# gems-0-01.net
KiCad netlist of a schematic drawn in EAGLE
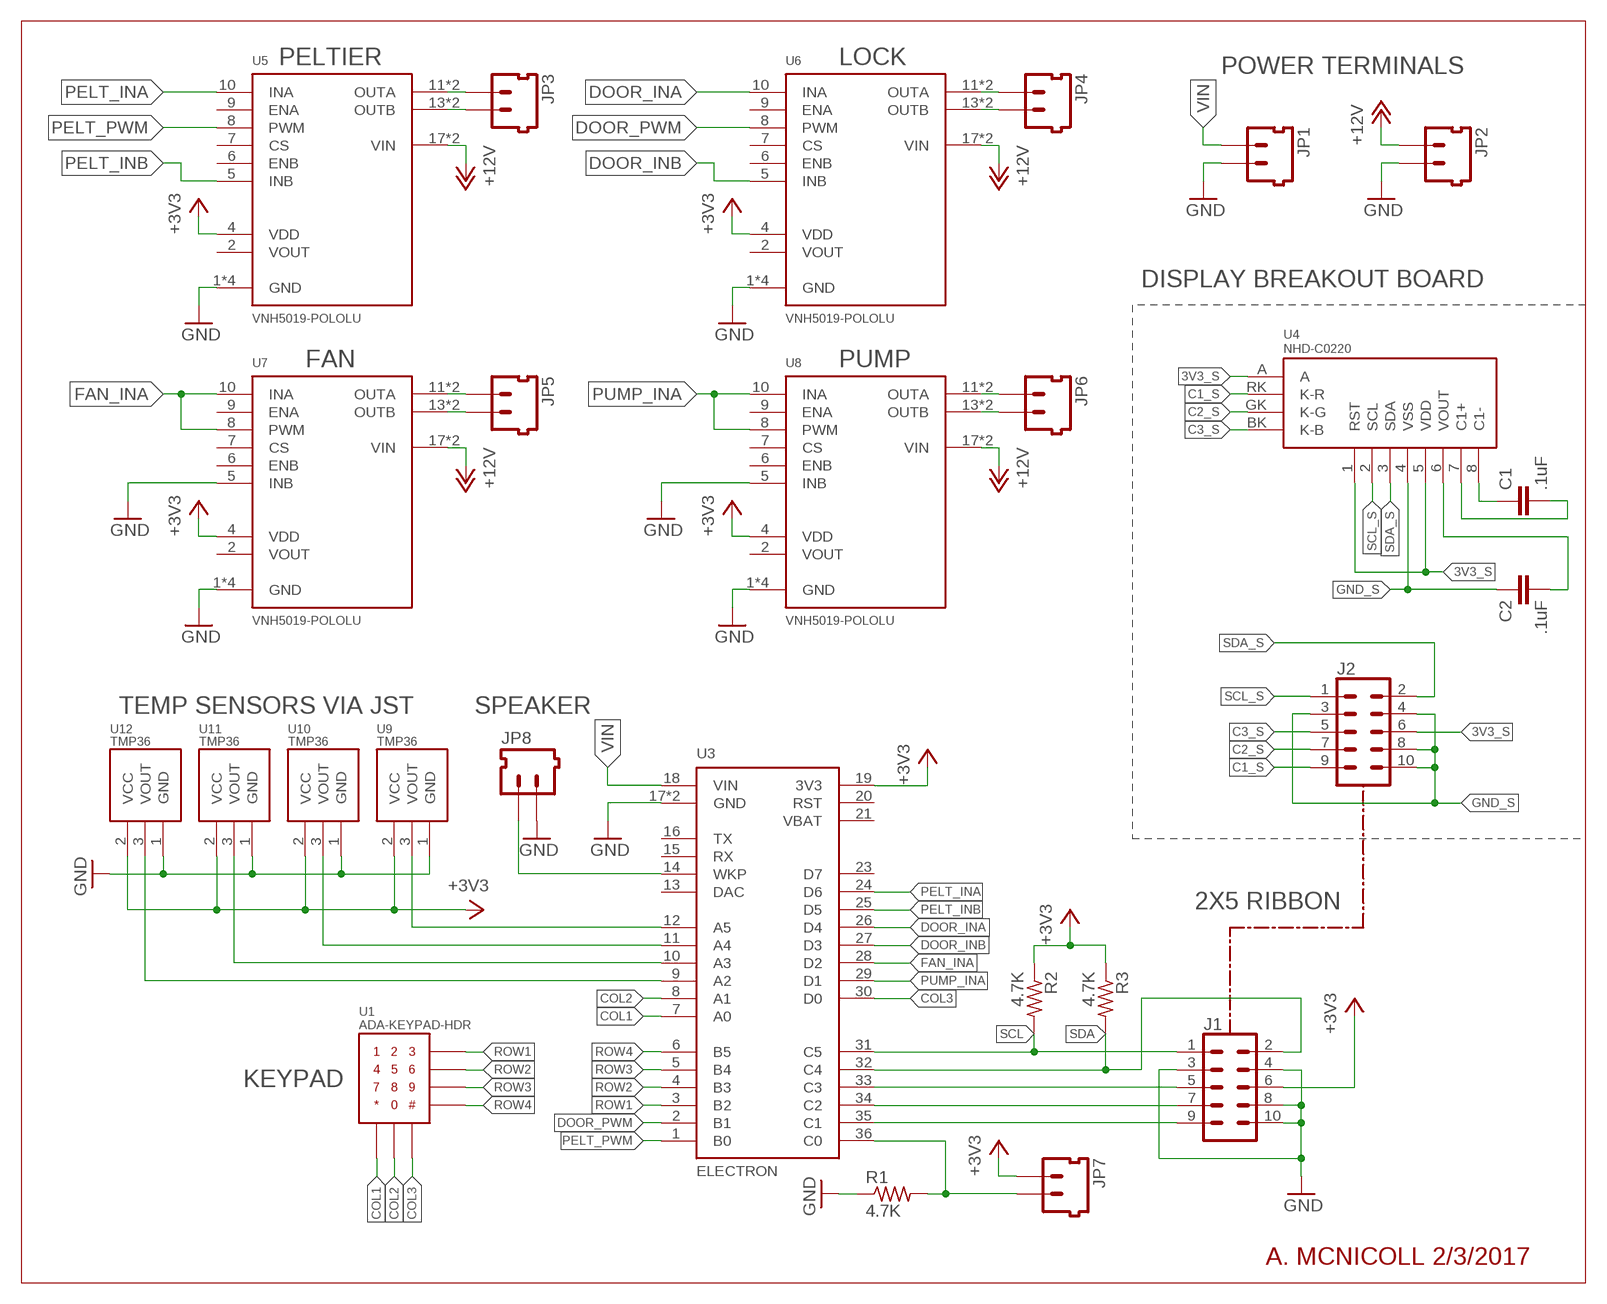
[diagram p0: schematic, sheet 1]

(export (version "E")
  (design (tool "Eeschema 10.0.6"))
  (components
    (comp (ref "C1")
      (value ".1uF")
      (footprint "eagle-import:C025-025X050")
      (libsource (lib "eagle-import") (part "C-EU025-025X050"))
    )
    (comp (ref "C2")
      (value ".1uF")
      (footprint "eagle-import:C025-025X050")
      (libsource (lib "eagle-import") (part "C-EU025-025X050"))
    )
    (comp (ref "J1")
      (value "CONN_05X2SHD-NS")
      (footprint "eagle-import:2X5-SHROUDED-NS")
      (libsource (lib "eagle-import") (part "CONN_05X2SHD-NS"))
    )
    (comp (ref "J2")
      (value "CONN_05X2SHD-NS")
      (footprint "eagle-import:2X5-SHROUDED-NS")
      (libsource (lib "eagle-import") (part "CONN_05X2SHD-NS"))
    )
    (comp (ref "JP1")
      (value "SCREW-TERMINAL-2PIN-5MM-KEYED")
      (footprint "eagle-import:SCREWTERMINAL-5MM-2-DIAG")
      (libsource (lib "eagle-import") (part "SCREW-TERMINAL-2PIN-5MM-KEYED"))
    )
    (comp (ref "JP2")
      (value "SCREW-TERMINAL-2PIN-5MM-KEYED")
      (footprint "eagle-import:SCREWTERMINAL-5MM-2-DIAG")
      (libsource (lib "eagle-import") (part "SCREW-TERMINAL-2PIN-5MM-KEYED"))
    )
    (comp (ref "JP3")
      (value "SCREW-TERMINAL-2PIN-5MM-KEYED")
      (footprint "eagle-import:SCREWTERMINAL-5MM-2-DIAG")
      (libsource (lib "eagle-import") (part "SCREW-TERMINAL-2PIN-5MM-KEYED"))
    )
    (comp (ref "JP4")
      (value "SCREW-TERMINAL-2PIN-5MM-KEYED")
      (footprint "eagle-import:SCREWTERMINAL-5MM-2-DIAG")
      (libsource (lib "eagle-import") (part "SCREW-TERMINAL-2PIN-5MM-KEYED"))
    )
    (comp (ref "JP5")
      (value "SCREW-TERMINAL-2PIN-5MM-KEYED")
      (footprint "eagle-import:SCREWTERMINAL-5MM-2-DIAG")
      (libsource (lib "eagle-import") (part "SCREW-TERMINAL-2PIN-5MM-KEYED"))
    )
    (comp (ref "JP6")
      (value "SCREW-TERMINAL-2PIN-5MM-KEYED")
      (footprint "eagle-import:SCREWTERMINAL-5MM-2-DIAG")
      (libsource (lib "eagle-import") (part "SCREW-TERMINAL-2PIN-5MM-KEYED"))
    )
    (comp (ref "JP7")
      (value "SCREW-TERMINAL-2PIN-5MM-KEYED")
      (footprint "eagle-import:SCREWTERMINAL-5MM-2-DIAG")
      (libsource (lib "eagle-import") (part "SCREW-TERMINAL-2PIN-5MM-KEYED"))
    )
    (comp (ref "JP8")
      (value "SCREW-TERMINAL-2PIN-5MM-KEYED")
      (footprint "eagle-import:SCREWTERMINAL-5MM-2-DIAG")
      (libsource (lib "eagle-import") (part "SCREW-TERMINAL-2PIN-5MM-KEYED"))
    )
    (comp (ref "R1")
      (value "4.7K")
      (footprint "eagle-import:0204_5")
      (libsource (lib "eagle-import") (part "R-US_0204/5"))
    )
    (comp (ref "R2")
      (value "4.7K")
      (footprint "eagle-import:0204_5")
      (libsource (lib "eagle-import") (part "R-US_0204/5"))
    )
    (comp (ref "R3")
      (value "4.7K")
      (footprint "eagle-import:0204_5")
      (libsource (lib "eagle-import") (part "R-US_0204/5"))
    )
    (comp (ref "U1")
      (value "ADA-KEYPAD-HDR")
      (footprint "eagle-import:HDR-7-STAGGERED")
      (libsource (lib "eagle-import") (part "ADA-KEYPAD-HDR"))
    )
    (comp (ref "U3")
      (value "ELECTRON")
      (footprint "eagle-import:ELECTRON")
      (libsource (lib "eagle-import") (part "ELECTRON"))
    )
    (comp (ref "U4")
      (value "NHD‐C0220")
      (footprint "eagle-import:NHD-C0220")
      (libsource (lib "eagle-import") (part "NHD‐C0220"))
    )
    (comp (ref "U5")
      (value "VNH5019-POLOLU")
      (footprint "eagle-import:VNH1519-CARRIER")
      (libsource (lib "eagle-import") (part "VNH5019-POLOLU"))
    )
    (comp (ref "U6")
      (value "VNH5019-POLOLU")
      (footprint "eagle-import:VNH1519-CARRIER")
      (libsource (lib "eagle-import") (part "VNH5019-POLOLU"))
    )
    (comp (ref "U7")
      (value "VNH5019-POLOLU")
      (footprint "eagle-import:VNH1519-CARRIER")
      (libsource (lib "eagle-import") (part "VNH5019-POLOLU"))
    )
    (comp (ref "U8")
      (value "VNH5019-POLOLU")
      (footprint "eagle-import:VNH1519-CARRIER")
      (libsource (lib "eagle-import") (part "VNH5019-POLOLU"))
    )
    (comp (ref "U9")
      (value "TMP36")
      (footprint "eagle-import:JST-3-PTH")
      (libsource (lib "eagle-import") (part "TMP36"))
    )
    (comp (ref "U10")
      (value "TMP36")
      (footprint "eagle-import:JST-3-PTH")
      (libsource (lib "eagle-import") (part "TMP36"))
    )
    (comp (ref "U11")
      (value "TMP36")
      (footprint "eagle-import:JST-3-PTH")
      (libsource (lib "eagle-import") (part "TMP36"))
    )
    (comp (ref "U12")
      (value "TMP36")
      (footprint "eagle-import:JST-3-PTH")
      (libsource (lib "eagle-import") (part "TMP36"))
    )
  )
  (nets
    (net (code "1") (name "+3V3") (class "Default")
      (node (ref "J1") (pin "6") (pinfunction "6_6") (pintype "passive"))
      (node (ref "JP7") (pin "F") (pinfunction "F_F") (pintype "passive"))
      (node (ref "R2") (pin "1") (pinfunction "1_1") (pintype "passive"))
      (node (ref "R3") (pin "1") (pinfunction "1_1") (pintype "passive"))
      (node (ref "U10") (pin "2") (pinfunction "VCC_2") (pintype "bidirectional"))
      (node (ref "U11") (pin "2") (pinfunction "VCC_2") (pintype "bidirectional"))
      (node (ref "U12") (pin "2") (pinfunction "VCC_2") (pintype "bidirectional"))
      (node (ref "U3") (pin "19") (pinfunction "3V3_19") (pintype "bidirectional"))
      (node (ref "U5") (pin "4") (pinfunction "VDD_4") (pintype "bidirectional"))
      (node (ref "U6") (pin "4") (pinfunction "VDD_4") (pintype "bidirectional"))
      (node (ref "U7") (pin "4") (pinfunction "VDD_4") (pintype "bidirectional"))
      (node (ref "U8") (pin "4") (pinfunction "VDD_4") (pintype "bidirectional"))
      (node (ref "U9") (pin "2") (pinfunction "VCC_2") (pintype "bidirectional"))
    )
    (net (code "2") (name "+12V") (class "Default")
      (node (ref "JP2") (pin "F") (pinfunction "F_F") (pintype "passive"))
      (node (ref "U5") (pin "17") (pinfunction "VIN_17") (pintype "bidirectional"))
      (node (ref "U5") (pin "18") (pinfunction "VIN_18") (pintype "bidirectional"))
      (node (ref "U6") (pin "17") (pinfunction "VIN_17") (pintype "bidirectional"))
      (node (ref "U6") (pin "18") (pinfunction "VIN_18") (pintype "bidirectional"))
      (node (ref "U7") (pin "17") (pinfunction "VIN_17") (pintype "bidirectional"))
      (node (ref "U7") (pin "18") (pinfunction "VIN_18") (pintype "bidirectional"))
      (node (ref "U8") (pin "17") (pinfunction "VIN_17") (pintype "bidirectional"))
      (node (ref "U8") (pin "18") (pinfunction "VIN_18") (pintype "bidirectional"))
    )
    (net (code "3") (name "3V3_S") (class "Default")
      (node (ref "J2") (pin "6") (pinfunction "6_6") (pintype "passive"))
      (node (ref "U4") (pin "1") (pinfunction "RST_1") (pintype "bidirectional"))
      (node (ref "U4") (pin "5") (pinfunction "VDD_5") (pintype "bidirectional"))
      (node (ref "U4") (pin "A") (pinfunction "A_A") (pintype "bidirectional"))
    )
    (net (code "4") (name "C1_S") (class "Default")
      (node (ref "J2") (pin "9") (pinfunction "9_9") (pintype "passive"))
      (node (ref "U4") (pin "RK") (pinfunction "K-R_RK") (pintype "bidirectional"))
    )
    (net (code "5") (name "C2_S") (class "Default")
      (node (ref "J2") (pin "7") (pinfunction "7_7") (pintype "passive"))
      (node (ref "U4") (pin "GK") (pinfunction "K-G_GK") (pintype "bidirectional"))
    )
    (net (code "6") (name "C3_S") (class "Default")
      (node (ref "J2") (pin "5") (pinfunction "5_5") (pintype "passive"))
      (node (ref "U4") (pin "BK") (pinfunction "K-B_BK") (pintype "bidirectional"))
    )
    (net (code "7") (name "COL1") (class "Default")
      (node (ref "U1") (pin "5") (pinfunction "C1_5") (pintype "bidirectional"))
      (node (ref "U3") (pin "7") (pinfunction "A0_7") (pintype "bidirectional"))
    )
    (net (code "8") (name "COL2") (class "Default")
      (node (ref "U1") (pin "6") (pinfunction "C2_6") (pintype "bidirectional"))
      (node (ref "U3") (pin "8") (pinfunction "A1_8") (pintype "bidirectional"))
    )
    (net (code "9") (name "COL3") (class "Default")
      (node (ref "U1") (pin "7") (pinfunction "C3_7") (pintype "bidirectional"))
      (node (ref "U3") (pin "30") (pinfunction "D0_30") (pintype "bidirectional"))
    )
    (net (code "10") (name "DOOR_INA") (class "Default")
      (node (ref "U3") (pin "26") (pinfunction "D4_26") (pintype "bidirectional"))
      (node (ref "U6") (pin "10") (pinfunction "INA_10") (pintype "bidirectional"))
    )
    (net (code "11") (name "DOOR_INB") (class "Default")
      (node (ref "U3") (pin "27") (pinfunction "D3_27") (pintype "bidirectional"))
      (node (ref "U6") (pin "5") (pinfunction "INB_5") (pintype "bidirectional"))
    )
    (net (code "12") (name "DOOR_PWM") (class "Default")
      (node (ref "U3") (pin "2") (pinfunction "B1_2") (pintype "bidirectional"))
      (node (ref "U6") (pin "8") (pinfunction "PWM_8") (pintype "bidirectional"))
    )
    (net (code "13") (name "FAN_INA") (class "Default")
      (node (ref "U3") (pin "28") (pinfunction "D2_28") (pintype "bidirectional"))
      (node (ref "U7") (pin "10") (pinfunction "INA_10") (pintype "bidirectional"))
      (node (ref "U7") (pin "8") (pinfunction "PWM_8") (pintype "bidirectional"))
    )
    (net (code "14") (name "GND") (class "Default")
      (node (ref "J1") (pin "10") (pinfunction "10_10") (pintype "passive"))
      (node (ref "J1") (pin "3") (pinfunction "3_3") (pintype "passive"))
      (node (ref "J1") (pin "4") (pinfunction "4_4") (pintype "passive"))
      (node (ref "J1") (pin "8") (pinfunction "8_8") (pintype "passive"))
      (node (ref "JP1") (pin "M") (pinfunction "M_M") (pintype "passive"))
      (node (ref "JP2") (pin "M") (pinfunction "M_M") (pintype "passive"))
      (node (ref "JP8") (pin "M") (pinfunction "M_M") (pintype "passive"))
      (node (ref "R1") (pin "1") (pinfunction "1_1") (pintype "passive"))
      (node (ref "U10") (pin "1") (pinfunction "GND_1") (pintype "bidirectional"))
      (node (ref "U11") (pin "1") (pinfunction "GND_1") (pintype "bidirectional"))
      (node (ref "U12") (pin "1") (pinfunction "GND_1") (pintype "bidirectional"))
      (node (ref "U3") (pin "17") (pinfunction "GND_17") (pintype "bidirectional"))
      (node (ref "U3") (pin "22") (pinfunction "GND_22") (pintype "bidirectional"))
      (node (ref "U5") (pin "1") (pinfunction "GND_1") (pintype "bidirectional"))
      (node (ref "U5") (pin "15") (pinfunction "GND_15") (pintype "bidirectional"))
      (node (ref "U5") (pin "16") (pinfunction "GND_16") (pintype "bidirectional"))
      (node (ref "U5") (pin "3") (pinfunction "GND_3") (pintype "bidirectional"))
      (node (ref "U6") (pin "1") (pinfunction "GND_1") (pintype "bidirectional"))
      (node (ref "U6") (pin "15") (pinfunction "GND_15") (pintype "bidirectional"))
      (node (ref "U6") (pin "16") (pinfunction "GND_16") (pintype "bidirectional"))
      (node (ref "U6") (pin "3") (pinfunction "GND_3") (pintype "bidirectional"))
      (node (ref "U7") (pin "1") (pinfunction "GND_1") (pintype "bidirectional"))
      (node (ref "U7") (pin "15") (pinfunction "GND_15") (pintype "bidirectional"))
      (node (ref "U7") (pin "16") (pinfunction "GND_16") (pintype "bidirectional"))
      (node (ref "U7") (pin "3") (pinfunction "GND_3") (pintype "bidirectional"))
      (node (ref "U7") (pin "5") (pinfunction "INB_5") (pintype "bidirectional"))
      (node (ref "U8") (pin "1") (pinfunction "GND_1") (pintype "bidirectional"))
      (node (ref "U8") (pin "15") (pinfunction "GND_15") (pintype "bidirectional"))
      (node (ref "U8") (pin "16") (pinfunction "GND_16") (pintype "bidirectional"))
      (node (ref "U8") (pin "3") (pinfunction "GND_3") (pintype "bidirectional"))
      (node (ref "U8") (pin "5") (pinfunction "INB_5") (pintype "bidirectional"))
      (node (ref "U9") (pin "1") (pinfunction "GND_1") (pintype "bidirectional"))
    )
    (net (code "15") (name "GND_S") (class "Default")
      (node (ref "C2") (pin "1") (pinfunction "1_1") (pintype "passive"))
      (node (ref "J2") (pin "10") (pinfunction "10_10") (pintype "passive"))
      (node (ref "J2") (pin "3") (pinfunction "3_3") (pintype "passive"))
      (node (ref "J2") (pin "4") (pinfunction "4_4") (pintype "passive"))
      (node (ref "J2") (pin "8") (pinfunction "8_8") (pintype "passive"))
      (node (ref "U4") (pin "4") (pinfunction "VSS_4") (pintype "bidirectional"))
    )
    (net (code "16") (name "Net-(JP3-PadF)") (class "Default")
      (node (ref "JP3") (pin "F") (pinfunction "F_F") (pintype "passive"))
      (node (ref "U5") (pin "11") (pinfunction "OUTA_11") (pintype "bidirectional"))
      (node (ref "U5") (pin "12") (pinfunction "OUTA_12") (pintype "bidirectional"))
    )
    (net (code "17") (name "Net-(JP3-PadM)") (class "Default")
      (node (ref "JP3") (pin "M") (pinfunction "M_M") (pintype "passive"))
      (node (ref "U5") (pin "13") (pinfunction "OUTB_13") (pintype "bidirectional"))
      (node (ref "U5") (pin "14") (pinfunction "OUTB_14") (pintype "bidirectional"))
    )
    (net (code "18") (name "Net-(JP4-PadF)") (class "Default")
      (node (ref "JP4") (pin "F") (pinfunction "F_F") (pintype "passive"))
      (node (ref "U6") (pin "11") (pinfunction "OUTA_11") (pintype "bidirectional"))
      (node (ref "U6") (pin "12") (pinfunction "OUTA_12") (pintype "bidirectional"))
    )
    (net (code "19") (name "Net-(JP4-PadM)") (class "Default")
      (node (ref "JP4") (pin "M") (pinfunction "M_M") (pintype "passive"))
      (node (ref "U6") (pin "13") (pinfunction "OUTB_13") (pintype "bidirectional"))
      (node (ref "U6") (pin "14") (pinfunction "OUTB_14") (pintype "bidirectional"))
    )
    (net (code "20") (name "Net-(JP5-PadF)") (class "Default")
      (node (ref "JP5") (pin "F") (pinfunction "F_F") (pintype "passive"))
      (node (ref "U7") (pin "11") (pinfunction "OUTA_11") (pintype "bidirectional"))
      (node (ref "U7") (pin "12") (pinfunction "OUTA_12") (pintype "bidirectional"))
    )
    (net (code "21") (name "Net-(JP5-PadM)") (class "Default")
      (node (ref "JP5") (pin "M") (pinfunction "M_M") (pintype "passive"))
      (node (ref "U7") (pin "13") (pinfunction "OUTB_13") (pintype "bidirectional"))
      (node (ref "U7") (pin "14") (pinfunction "OUTB_14") (pintype "bidirectional"))
    )
    (net (code "22") (name "Net-(JP6-PadF)") (class "Default")
      (node (ref "JP6") (pin "F") (pinfunction "F_F") (pintype "passive"))
      (node (ref "U8") (pin "11") (pinfunction "OUTA_11") (pintype "bidirectional"))
      (node (ref "U8") (pin "12") (pinfunction "OUTA_12") (pintype "bidirectional"))
    )
    (net (code "23") (name "Net-(JP6-PadM)") (class "Default")
      (node (ref "JP6") (pin "M") (pinfunction "M_M") (pintype "passive"))
      (node (ref "U8") (pin "13") (pinfunction "OUTB_13") (pintype "bidirectional"))
      (node (ref "U8") (pin "14") (pinfunction "OUTB_14") (pintype "bidirectional"))
    )
    (net (code "24") (name "Net-(U3-A5)") (class "Default")
      (node (ref "U3") (pin "12") (pinfunction "A5_12") (pintype "bidirectional"))
      (node (ref "U9") (pin "3") (pinfunction "VOUT_3") (pintype "bidirectional"))
    )
    (net (code "25") (name "Net-(U3-C0)") (class "Default")
      (node (ref "JP7") (pin "M") (pinfunction "M_M") (pintype "passive"))
      (node (ref "R1") (pin "2") (pinfunction "2_2") (pintype "passive"))
      (node (ref "U3") (pin "36") (pinfunction "C0_36") (pintype "bidirectional"))
    )
    (net (code "26") (name "Net-(U3-C1)") (class "Default")
      (node (ref "J1") (pin "9") (pinfunction "9_9") (pintype "passive"))
      (node (ref "U3") (pin "35") (pinfunction "C1_35") (pintype "bidirectional"))
    )
    (net (code "27") (name "Net-(U3-C2)") (class "Default")
      (node (ref "J1") (pin "7") (pinfunction "7_7") (pintype "passive"))
      (node (ref "U3") (pin "34") (pinfunction "C2_34") (pintype "bidirectional"))
    )
    (net (code "28") (name "Net-(U3-C3)") (class "Default")
      (node (ref "J1") (pin "5") (pinfunction "5_5") (pintype "passive"))
      (node (ref "U3") (pin "33") (pinfunction "C3_33") (pintype "bidirectional"))
    )
    (net (code "29") (name "Net-(U3-WKP)") (class "Default")
      (node (ref "JP8") (pin "F") (pinfunction "F_F") (pintype "passive"))
      (node (ref "U3") (pin "14") (pinfunction "WKP_14") (pintype "bidirectional"))
    )
    (net (code "30") (name "Net-(U4-C1+)") (class "Default")
      (node (ref "C1") (pin "2") (pinfunction "2_2") (pintype "passive"))
      (node (ref "U4") (pin "7") (pinfunction "C1+_7") (pintype "bidirectional"))
    )
    (net (code "31") (name "Net-(U4-C1-)") (class "Default")
      (node (ref "C1") (pin "1") (pinfunction "1_1") (pintype "passive"))
      (node (ref "U4") (pin "8") (pinfunction "C1-_8") (pintype "bidirectional"))
    )
    (net (code "32") (name "Net-(U4-VOUT)") (class "Default")
      (node (ref "C2") (pin "2") (pinfunction "2_2") (pintype "passive"))
      (node (ref "U4") (pin "6") (pinfunction "VOUT_6") (pintype "bidirectional"))
    )
    (net (code "33") (name "Net-(U10-VOUT)") (class "Default")
      (node (ref "U10") (pin "3") (pinfunction "VOUT_3") (pintype "bidirectional"))
      (node (ref "U3") (pin "11") (pinfunction "A4_11") (pintype "bidirectional"))
    )
    (net (code "34") (name "Net-(U11-VOUT)") (class "Default")
      (node (ref "U11") (pin "3") (pinfunction "VOUT_3") (pintype "bidirectional"))
      (node (ref "U3") (pin "10") (pinfunction "A3_10") (pintype "bidirectional"))
    )
    (net (code "35") (name "Net-(U12-VOUT)") (class "Default")
      (node (ref "U12") (pin "3") (pinfunction "VOUT_3") (pintype "bidirectional"))
      (node (ref "U3") (pin "9") (pinfunction "A2_9") (pintype "bidirectional"))
    )
    (net (code "36") (name "PELT_INA") (class "Default")
      (node (ref "U3") (pin "24") (pinfunction "D6_24") (pintype "bidirectional"))
      (node (ref "U5") (pin "10") (pinfunction "INA_10") (pintype "bidirectional"))
    )
    (net (code "37") (name "PELT_INB") (class "Default")
      (node (ref "U3") (pin "25") (pinfunction "D5_25") (pintype "bidirectional"))
      (node (ref "U5") (pin "5") (pinfunction "INB_5") (pintype "bidirectional"))
    )
    (net (code "38") (name "PELT_PWM") (class "Default")
      (node (ref "U3") (pin "1") (pinfunction "B0_1") (pintype "bidirectional"))
      (node (ref "U5") (pin "8") (pinfunction "PWM_8") (pintype "bidirectional"))
    )
    (net (code "39") (name "PUMP_INA") (class "Default")
      (node (ref "U3") (pin "29") (pinfunction "D1_29") (pintype "bidirectional"))
      (node (ref "U8") (pin "10") (pinfunction "INA_10") (pintype "bidirectional"))
      (node (ref "U8") (pin "8") (pinfunction "PWM_8") (pintype "bidirectional"))
    )
    (net (code "40") (name "ROW1") (class "Default")
      (node (ref "U1") (pin "1") (pinfunction "R1_1") (pintype "bidirectional"))
      (node (ref "U3") (pin "3") (pinfunction "B2_3") (pintype "bidirectional"))
    )
    (net (code "41") (name "ROW2") (class "Default")
      (node (ref "U1") (pin "2") (pinfunction "R2_2") (pintype "bidirectional"))
      (node (ref "U3") (pin "4") (pinfunction "B3_4") (pintype "bidirectional"))
    )
    (net (code "42") (name "ROW3") (class "Default")
      (node (ref "U1") (pin "3") (pinfunction "R3_3") (pintype "bidirectional"))
      (node (ref "U3") (pin "5") (pinfunction "B4_5") (pintype "bidirectional"))
    )
    (net (code "43") (name "ROW4") (class "Default")
      (node (ref "U1") (pin "4") (pinfunction "R4_4") (pintype "bidirectional"))
      (node (ref "U3") (pin "6") (pinfunction "B5_6") (pintype "bidirectional"))
    )
    (net (code "44") (name "SCL") (class "Default")
      (node (ref "J1") (pin "1") (pinfunction "1_1") (pintype "passive"))
      (node (ref "R2") (pin "2") (pinfunction "2_2") (pintype "passive"))
      (node (ref "U3") (pin "31") (pinfunction "C5_31") (pintype "bidirectional"))
    )
    (net (code "45") (name "SCL_S") (class "Default")
      (node (ref "J2") (pin "1") (pinfunction "1_1") (pintype "passive"))
      (node (ref "U4") (pin "2") (pinfunction "SCL_2") (pintype "bidirectional"))
    )
    (net (code "46") (name "SDA") (class "Default")
      (node (ref "J1") (pin "2") (pinfunction "2_2") (pintype "passive"))
      (node (ref "R3") (pin "2") (pinfunction "2_2") (pintype "passive"))
      (node (ref "U3") (pin "32") (pinfunction "C4_32") (pintype "bidirectional"))
    )
    (net (code "47") (name "SDA_S") (class "Default")
      (node (ref "J2") (pin "2") (pinfunction "2_2") (pintype "passive"))
      (node (ref "U4") (pin "3") (pinfunction "SDA_3") (pintype "bidirectional"))
    )
    (net (code "48") (name "VIN") (class "Default")
      (node (ref "JP1") (pin "F") (pinfunction "F_F") (pintype "passive"))
      (node (ref "U3") (pin "18") (pinfunction "VIN_18") (pintype "bidirectional"))
    )
    (net (code "49") (name "unconnected-(U3-D7-Pad23)") (class "Default")
      (node (ref "U3") (pin "23") (pinfunction "D7_23") (pintype "bidirectional"))
    )
    (net (code "50") (name "unconnected-(U3-DAC-Pad13)") (class "Default")
      (node (ref "U3") (pin "13") (pinfunction "DAC_13") (pintype "bidirectional"))
    )
    (net (code "51") (name "unconnected-(U3-RST-Pad20)") (class "Default")
      (node (ref "U3") (pin "20") (pinfunction "RST_20") (pintype "bidirectional"))
    )
    (net (code "52") (name "unconnected-(U3-RX-Pad15)") (class "Default")
      (node (ref "U3") (pin "15") (pinfunction "RX_15") (pintype "bidirectional"))
    )
    (net (code "53") (name "unconnected-(U3-TX-Pad16)") (class "Default")
      (node (ref "U3") (pin "16") (pinfunction "TX_16") (pintype "bidirectional"))
    )
    (net (code "54") (name "unconnected-(U3-VBAT-Pad21)") (class "Default")
      (node (ref "U3") (pin "21") (pinfunction "VBAT_21") (pintype "bidirectional"))
    )
    (net (code "55") (name "unconnected-(U5-CS-Pad7)") (class "Default")
      (node (ref "U5") (pin "7") (pinfunction "CS_7") (pintype "bidirectional"))
    )
    (net (code "56") (name "unconnected-(U5-ENA-Pad9)") (class "Default")
      (node (ref "U5") (pin "9") (pinfunction "ENA_9") (pintype "bidirectional"))
    )
    (net (code "57") (name "unconnected-(U5-ENB-Pad6)") (class "Default")
      (node (ref "U5") (pin "6") (pinfunction "ENB_6") (pintype "bidirectional"))
    )
    (net (code "58") (name "unconnected-(U5-VOUT-Pad2)") (class "Default")
      (node (ref "U5") (pin "2") (pinfunction "VOUT_2") (pintype "bidirectional"))
    )
    (net (code "59") (name "unconnected-(U6-CS-Pad7)") (class "Default")
      (node (ref "U6") (pin "7") (pinfunction "CS_7") (pintype "bidirectional"))
    )
    (net (code "60") (name "unconnected-(U6-ENA-Pad9)") (class "Default")
      (node (ref "U6") (pin "9") (pinfunction "ENA_9") (pintype "bidirectional"))
    )
    (net (code "61") (name "unconnected-(U6-ENB-Pad6)") (class "Default")
      (node (ref "U6") (pin "6") (pinfunction "ENB_6") (pintype "bidirectional"))
    )
    (net (code "62") (name "unconnected-(U6-VOUT-Pad2)") (class "Default")
      (node (ref "U6") (pin "2") (pinfunction "VOUT_2") (pintype "bidirectional"))
    )
    (net (code "63") (name "unconnected-(U7-CS-Pad7)") (class "Default")
      (node (ref "U7") (pin "7") (pinfunction "CS_7") (pintype "bidirectional"))
    )
    (net (code "64") (name "unconnected-(U7-ENA-Pad9)") (class "Default")
      (node (ref "U7") (pin "9") (pinfunction "ENA_9") (pintype "bidirectional"))
    )
    (net (code "65") (name "unconnected-(U7-ENB-Pad6)") (class "Default")
      (node (ref "U7") (pin "6") (pinfunction "ENB_6") (pintype "bidirectional"))
    )
    (net (code "66") (name "unconnected-(U7-VOUT-Pad2)") (class "Default")
      (node (ref "U7") (pin "2") (pinfunction "VOUT_2") (pintype "bidirectional"))
    )
    (net (code "67") (name "unconnected-(U8-CS-Pad7)") (class "Default")
      (node (ref "U8") (pin "7") (pinfunction "CS_7") (pintype "bidirectional"))
    )
    (net (code "68") (name "unconnected-(U8-ENA-Pad9)") (class "Default")
      (node (ref "U8") (pin "9") (pinfunction "ENA_9") (pintype "bidirectional"))
    )
    (net (code "69") (name "unconnected-(U8-ENB-Pad6)") (class "Default")
      (node (ref "U8") (pin "6") (pinfunction "ENB_6") (pintype "bidirectional"))
    )
    (net (code "70") (name "unconnected-(U8-VOUT-Pad2)") (class "Default")
      (node (ref "U8") (pin "2") (pinfunction "VOUT_2") (pintype "bidirectional"))
    )
  )
)
